# Encoder.net
KiCad netlist of a schematic drawn in EAGLE
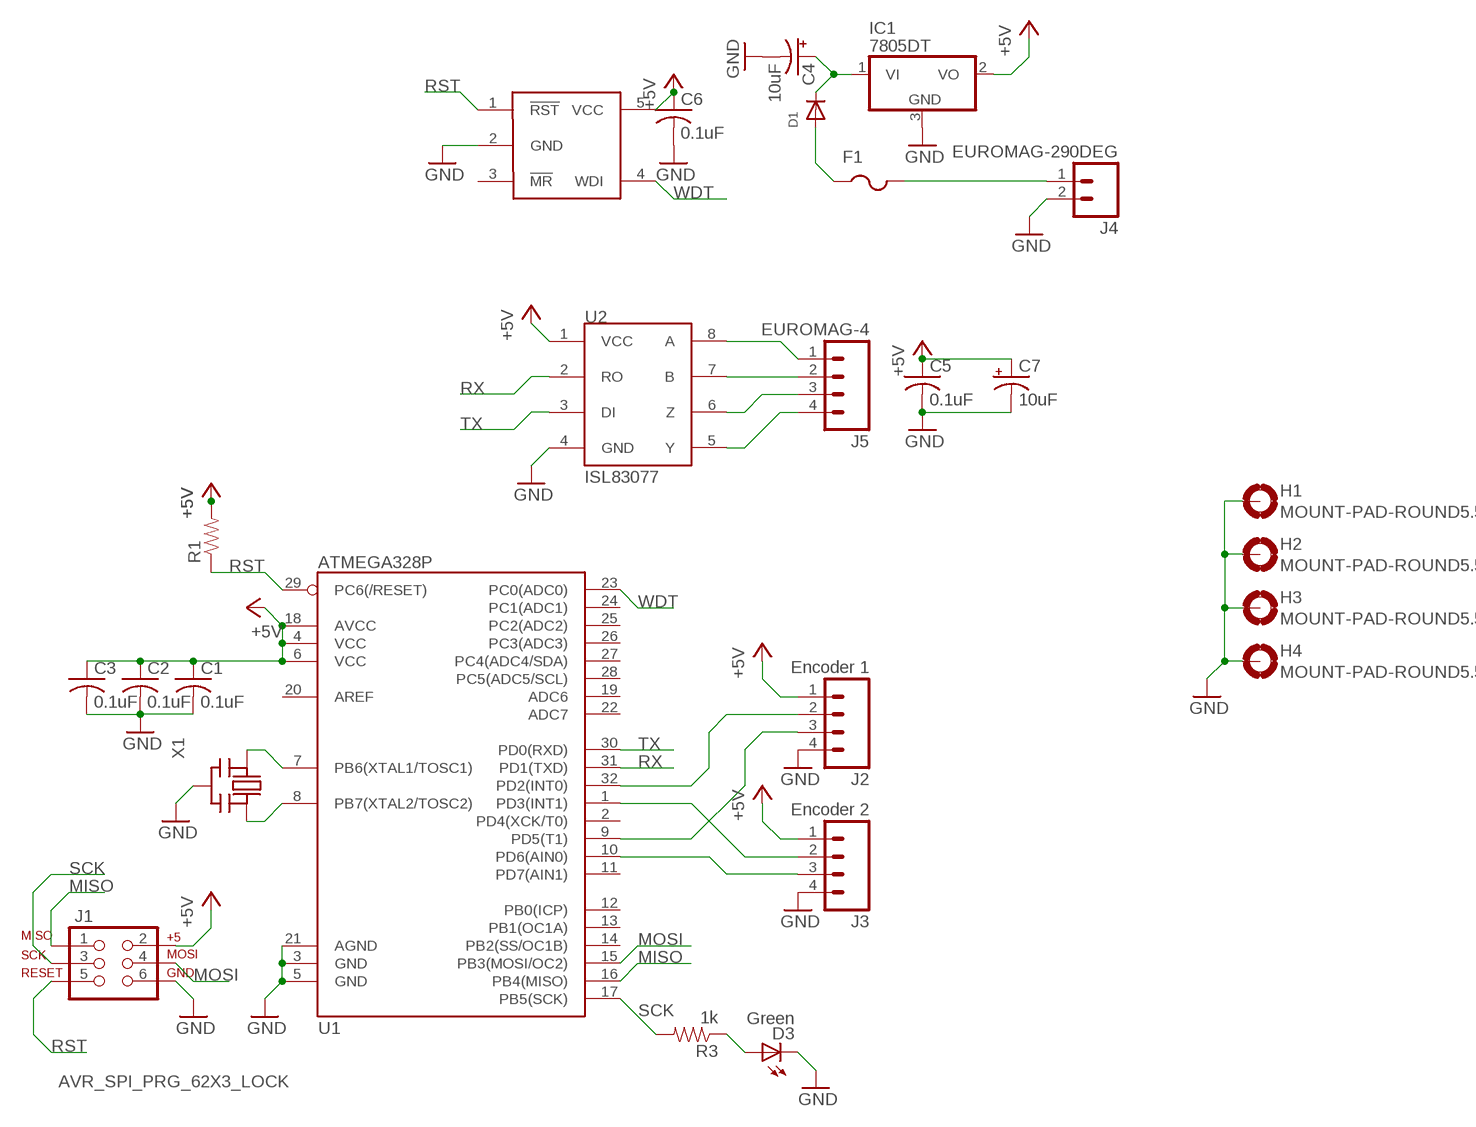
[diagram p0: schematic, sheet 1]

(export (version "E")
  (design (tool "Eeschema 10.0.6"))
  (components
    (comp (ref "C1")
      (value "0.1uF")
      (footprint "eagle-import:C0805")
      (libsource (lib "eagle-import") (part "C-USC0805"))
    )
    (comp (ref "C2")
      (value "0.1uF")
      (footprint "eagle-import:C0805")
      (libsource (lib "eagle-import") (part "C-USC0805"))
    )
    (comp (ref "C3")
      (value "0.1uF")
      (footprint "eagle-import:C0805")
      (libsource (lib "eagle-import") (part "C-USC0805"))
    )
    (comp (ref "C4")
      (value "10uF")
      (footprint "eagle-import:CT6032")
      (libsource (lib "eagle-import") (part "CPOL-USCT6032"))
    )
    (comp (ref "C5")
      (value "0.1uF")
      (footprint "eagle-import:C0805")
      (libsource (lib "eagle-import") (part "C-USC0805"))
    )
    (comp (ref "C6")
      (value "0.1uF")
      (footprint "eagle-import:C0805")
      (libsource (lib "eagle-import") (part "C-USC0805"))
    )
    (comp (ref "C7")
      (value "10uF")
      (footprint "eagle-import:CT6032")
      (libsource (lib "eagle-import") (part "CPOL-USCT6032"))
    )
    (comp (ref "D1")
      (value "DIODESMA")
      (footprint "eagle-import:SMADIODE")
      (libsource (lib "eagle-import") (part "DIODESMA"))
    )
    (comp (ref "D3")
      (value "Green")
      (footprint "eagle-import:LED-0603")
      (libsource (lib "eagle-import") (part "LED0603"))
    )
    (comp (ref "F1")
      (value "PTCFUSE-1206")
      (footprint "eagle-import:R1206")
      (libsource (lib "eagle-import") (part "PTCFUSE-1206"))
    )
    (comp (ref "H1")
      (value "MOUNT-PAD-ROUND5.5")
      (footprint "eagle-import:5,5-PAD")
      (libsource (lib "eagle-import") (part "MOUNT-PAD-ROUND5.5"))
    )
    (comp (ref "H2")
      (value "MOUNT-PAD-ROUND5.5")
      (footprint "eagle-import:5,5-PAD")
      (libsource (lib "eagle-import") (part "MOUNT-PAD-ROUND5.5"))
    )
    (comp (ref "H3")
      (value "MOUNT-PAD-ROUND5.5")
      (footprint "eagle-import:5,5-PAD")
      (libsource (lib "eagle-import") (part "MOUNT-PAD-ROUND5.5"))
    )
    (comp (ref "H4")
      (value "MOUNT-PAD-ROUND5.5")
      (footprint "eagle-import:5,5-PAD")
      (libsource (lib "eagle-import") (part "MOUNT-PAD-ROUND5.5"))
    )
    (comp (ref "IC1")
      (value "7805DT")
      (footprint "eagle-import:TO252")
      (libsource (lib "eagle-import") (part "78DT05"))
    )
    (comp (ref "J1")
      (value "AVR_SPI_PRG_62X3_LOCK")
      (footprint "eagle-import:2X3_LOCK")
      (libsource (lib "eagle-import") (part "AVR_SPI_PRG_62X3_LOCK"))
    )
    (comp (ref "J2")
      (value "Encoder 1")
      (footprint "eagle-import:M4")
      (libsource (lib "eagle-import") (part "EUROMAG-4"))
    )
    (comp (ref "J3")
      (value "Encoder 2")
      (footprint "eagle-import:M4")
      (libsource (lib "eagle-import") (part "EUROMAG-4"))
    )
    (comp (ref "J4")
      (value "EUROMAG-290DEG")
      (footprint "eagle-import:M2")
      (libsource (lib "eagle-import") (part "EUROMAG-290DEG"))
    )
    (comp (ref "J5")
      (value "EUROMAG-4")
      (footprint "eagle-import:M4")
      (libsource (lib "eagle-import") (part "EUROMAG-4"))
    )
    (comp (ref "R1")
      (value "RESISTOR0805-RES")
      (footprint "eagle-import:0805")
      (libsource (lib "eagle-import") (part "RESISTOR0805-RES"))
    )
    (comp (ref "R3")
      (value "1k")
      (footprint "eagle-import:0805")
      (libsource (lib "eagle-import") (part "RESISTOR0805-RES"))
    )
    (comp (ref "U$18")
      (value "MAX823")
      (footprint "eagle-import:SOT23-5L")
      (libsource (lib "eagle-import") (part "MAX823"))
    )
    (comp (ref "U1")
      (value "ATMEGA328P")
      (footprint "eagle-import:TQFP32-08")
      (libsource (lib "eagle-import") (part "ATMEGA328_SMT"))
    )
    (comp (ref "U2")
      (value "ISL83077")
      (footprint "eagle-import:SO08")
      (libsource (lib "eagle-import") (part "ISL83077"))
    )
    (comp (ref "X1")
      (value "CERMOSCILL-AWCSR")
      (footprint "eagle-import:AWCSR")
      (libsource (lib "eagle-import") (part "CERMOSCILL-AWCSR"))
    )
  )
  (nets
    (net (code "1") (name "+5V") (class "Default")
      (node (ref "C1") (pin "1") (pinfunction "1_1") (pintype "passive"))
      (node (ref "C2") (pin "1") (pinfunction "1_1") (pintype "passive"))
      (node (ref "C3") (pin "1") (pinfunction "1_1") (pintype "passive"))
      (node (ref "C5") (pin "1") (pinfunction "1_1") (pintype "passive"))
      (node (ref "C6") (pin "1") (pinfunction "1_1") (pintype "passive"))
      (node (ref "C7") (pin "+") (pinfunction "+_+") (pintype "passive"))
      (node (ref "IC1") (pin "2") (pinfunction "VO_2") (pintype "passive"))
      (node (ref "J1") (pin "2") (pinfunction "2_2") (pintype "passive"))
      (node (ref "J2") (pin "1") (pinfunction "1_1") (pintype "passive"))
      (node (ref "J3") (pin "1") (pinfunction "1_1") (pintype "passive"))
      (node (ref "R1") (pin "2") (pinfunction "2_2") (pintype "passive"))
      (node (ref "U$18") (pin "5") (pinfunction "VCC_5") (pintype "bidirectional"))
      (node (ref "U1") (pin "18") (pinfunction "AVCC_18") (pintype "bidirectional"))
      (node (ref "U1") (pin "4") (pinfunction "VCC_4") (pintype "bidirectional"))
      (node (ref "U1") (pin "6") (pinfunction "VCC_6") (pintype "bidirectional"))
      (node (ref "U2") (pin "1") (pinfunction "VCC_1") (pintype "bidirectional"))
    )
    (net (code "2") (name "/MISO") (class "Default")
      (node (ref "J1") (pin "1") (pinfunction "1_1") (pintype "passive"))
      (node (ref "U1") (pin "16") (pinfunction "PB4(MISO)_16") (pintype "bidirectional"))
    )
    (net (code "3") (name "/MOSI") (class "Default")
      (node (ref "J1") (pin "4") (pinfunction "4_4") (pintype "passive"))
      (node (ref "U1") (pin "15") (pinfunction "PB3(MOSI/OC2)_15") (pintype "bidirectional"))
    )
    (net (code "4") (name "/RST") (class "Default")
      (node (ref "J1") (pin "5") (pinfunction "5_5") (pintype "passive"))
      (node (ref "R1") (pin "1") (pinfunction "1_1") (pintype "passive"))
      (node (ref "U$18") (pin "1") (pinfunction "~{RST}_1") (pintype "bidirectional"))
      (node (ref "U1") (pin "29") (pinfunction "PC6(/RESET)_29") (pintype "bidirectional"))
    )
    (net (code "5") (name "/RX") (class "Default")
      (node (ref "U1") (pin "31") (pinfunction "PD1(TXD)_31") (pintype "bidirectional"))
      (node (ref "U2") (pin "2") (pinfunction "RO_2") (pintype "bidirectional"))
    )
    (net (code "6") (name "/SCK") (class "Default")
      (node (ref "J1") (pin "3") (pinfunction "3_3") (pintype "passive"))
      (node (ref "R3") (pin "2") (pinfunction "2_2") (pintype "passive"))
      (node (ref "U1") (pin "17") (pinfunction "PB5(SCK)_17") (pintype "bidirectional"))
    )
    (net (code "7") (name "/TX") (class "Default")
      (node (ref "U1") (pin "30") (pinfunction "PD0(RXD)_30") (pintype "bidirectional"))
      (node (ref "U2") (pin "3") (pinfunction "DI_3") (pintype "bidirectional"))
    )
    (net (code "8") (name "/WDT") (class "Default")
      (node (ref "U$18") (pin "4") (pinfunction "WDI_4") (pintype "bidirectional"))
      (node (ref "U1") (pin "23") (pinfunction "PC0(ADC0)_23") (pintype "bidirectional"))
    )
    (net (code "9") (name "GND") (class "Default")
      (node (ref "C1") (pin "2") (pinfunction "2_2") (pintype "passive"))
      (node (ref "C2") (pin "2") (pinfunction "2_2") (pintype "passive"))
      (node (ref "C3") (pin "2") (pinfunction "2_2") (pintype "passive"))
      (node (ref "C4") (pin "-") (pinfunction "-_-") (pintype "passive"))
      (node (ref "C5") (pin "2") (pinfunction "2_2") (pintype "passive"))
      (node (ref "C6") (pin "2") (pinfunction "2_2") (pintype "passive"))
      (node (ref "C7") (pin "-") (pinfunction "-_-") (pintype "passive"))
      (node (ref "D3") (pin "C") (pinfunction "C_C") (pintype "passive"))
      (node (ref "H1") (pin "B5,5") (pinfunction "MOUNT_B5,5") (pintype "passive"))
      (node (ref "H2") (pin "B5,5") (pinfunction "MOUNT_B5,5") (pintype "passive"))
      (node (ref "H3") (pin "B5,5") (pinfunction "MOUNT_B5,5") (pintype "passive"))
      (node (ref "H4") (pin "B5,5") (pinfunction "MOUNT_B5,5") (pintype "passive"))
      (node (ref "IC1") (pin "3") (pinfunction "GND_3") (pintype "passive"))
      (node (ref "J1") (pin "6") (pinfunction "6_6") (pintype "passive"))
      (node (ref "J2") (pin "4") (pinfunction "4_4") (pintype "passive"))
      (node (ref "J3") (pin "4") (pinfunction "4_4") (pintype "passive"))
      (node (ref "J4") (pin "2") (pinfunction "2_2") (pintype "passive"))
      (node (ref "U$18") (pin "2") (pinfunction "GND_2") (pintype "bidirectional"))
      (node (ref "U1") (pin "21") (pinfunction "AGND_21") (pintype "bidirectional"))
      (node (ref "U1") (pin "3") (pinfunction "GND_3") (pintype "bidirectional"))
      (node (ref "U1") (pin "5") (pinfunction "GND_5") (pintype "bidirectional"))
      (node (ref "U2") (pin "4") (pinfunction "GND_4") (pintype "bidirectional"))
      (node (ref "X1") (pin "2") (pinfunction "GND_2") (pintype "bidirectional"))
    )
    (net (code "10") (name "Net-(D1-PadA)") (class "Default")
      (node (ref "D1") (pin "A") (pinfunction "A_A") (pintype "passive"))
      (node (ref "F1") (pin "1") (pinfunction "1_1") (pintype "passive"))
    )
    (net (code "11") (name "Net-(D3-PadA)") (class "Default")
      (node (ref "D3") (pin "A") (pinfunction "A_A") (pintype "passive"))
      (node (ref "R3") (pin "1") (pinfunction "1_1") (pintype "passive"))
    )
    (net (code "12") (name "Net-(F1-Pad2)") (class "Default")
      (node (ref "F1") (pin "2") (pinfunction "2_2") (pintype "passive"))
      (node (ref "J4") (pin "1") (pinfunction "1_1") (pintype "passive"))
    )
    (net (code "13") (name "Net-(IC1-VI)") (class "Default")
      (node (ref "C4") (pin "+") (pinfunction "+_+") (pintype "passive"))
      (node (ref "D1") (pin "C") (pinfunction "C_C") (pintype "passive"))
      (node (ref "IC1") (pin "1") (pinfunction "VI_1") (pintype "input"))
    )
    (net (code "14") (name "Net-(U1-PB6(XTAL1{slash}TOSC1))") (class "Default")
      (node (ref "U1") (pin "7") (pinfunction "PB6(XTAL1/TOSC1)_7") (pintype "bidirectional"))
      (node (ref "X1") (pin "1") (pinfunction "IN_1") (pintype "bidirectional"))
    )
    (net (code "15") (name "Net-(U1-PB7(XTAL2{slash}TOSC2))") (class "Default")
      (node (ref "U1") (pin "8") (pinfunction "PB7(XTAL2/TOSC2)_8") (pintype "bidirectional"))
      (node (ref "X1") (pin "3") (pinfunction "OUT_3") (pintype "bidirectional"))
    )
    (net (code "16") (name "Net-(U1-PD2(INT0))") (class "Default")
      (node (ref "J2") (pin "2") (pinfunction "2_2") (pintype "passive"))
      (node (ref "U1") (pin "32") (pinfunction "PD2(INT0)_32") (pintype "bidirectional"))
    )
    (net (code "17") (name "Net-(U1-PD3(INT1))") (class "Default")
      (node (ref "J3") (pin "2") (pinfunction "2_2") (pintype "passive"))
      (node (ref "U1") (pin "1") (pinfunction "PD3(INT1)_1") (pintype "bidirectional"))
    )
    (net (code "18") (name "Net-(U1-PD5(T1))") (class "Default")
      (node (ref "J2") (pin "3") (pinfunction "3_3") (pintype "passive"))
      (node (ref "U1") (pin "9") (pinfunction "PD5(T1)_9") (pintype "bidirectional"))
    )
    (net (code "19") (name "Net-(U1-PD6(AIN0))") (class "Default")
      (node (ref "J3") (pin "3") (pinfunction "3_3") (pintype "passive"))
      (node (ref "U1") (pin "10") (pinfunction "PD6(AIN0)_10") (pintype "bidirectional"))
    )
    (net (code "20") (name "Net-(U2-A)") (class "Default")
      (node (ref "J5") (pin "1") (pinfunction "1_1") (pintype "passive"))
      (node (ref "U2") (pin "8") (pinfunction "A_8") (pintype "bidirectional"))
    )
    (net (code "21") (name "Net-(U2-B)") (class "Default")
      (node (ref "J5") (pin "2") (pinfunction "2_2") (pintype "passive"))
      (node (ref "U2") (pin "7") (pinfunction "B_7") (pintype "bidirectional"))
    )
    (net (code "22") (name "Net-(U2-Y)") (class "Default")
      (node (ref "J5") (pin "4") (pinfunction "4_4") (pintype "passive"))
      (node (ref "U2") (pin "5") (pinfunction "Y_5") (pintype "bidirectional"))
    )
    (net (code "23") (name "Net-(U2-Z)") (class "Default")
      (node (ref "J5") (pin "3") (pinfunction "3_3") (pintype "passive"))
      (node (ref "U2") (pin "6") (pinfunction "Z_6") (pintype "bidirectional"))
    )
    (net (code "24") (name "unconnected-(U$18-~{MR}-Pad3)") (class "Default")
      (node (ref "U$18") (pin "3") (pinfunction "~{MR}_3") (pintype "bidirectional"))
    )
    (net (code "25") (name "unconnected-(U1-ADC6-Pad19)") (class "Default")
      (node (ref "U1") (pin "19") (pinfunction "ADC6_19") (pintype "bidirectional"))
    )
    (net (code "26") (name "unconnected-(U1-ADC7-Pad22)") (class "Default")
      (node (ref "U1") (pin "22") (pinfunction "ADC7_22") (pintype "bidirectional"))
    )
    (net (code "27") (name "unconnected-(U1-AREF-Pad20)") (class "Default")
      (node (ref "U1") (pin "20") (pinfunction "AREF_20") (pintype "bidirectional"))
    )
    (net (code "28") (name "unconnected-(U1-PB0(ICP)-Pad12)") (class "Default")
      (node (ref "U1") (pin "12") (pinfunction "PB0(ICP)_12") (pintype "bidirectional"))
    )
    (net (code "29") (name "unconnected-(U1-PB1(OC1A)-Pad13)") (class "Default")
      (node (ref "U1") (pin "13") (pinfunction "PB1(OC1A)_13") (pintype "bidirectional"))
    )
    (net (code "30") (name "unconnected-(U1-PB2(SS{slash}OC1B)-Pad14)") (class "Default")
      (node (ref "U1") (pin "14") (pinfunction "PB2(SS/OC1B)_14") (pintype "bidirectional"))
    )
    (net (code "31") (name "unconnected-(U1-PC1(ADC1)-Pad24)") (class "Default")
      (node (ref "U1") (pin "24") (pinfunction "PC1(ADC1)_24") (pintype "bidirectional"))
    )
    (net (code "32") (name "unconnected-(U1-PC2(ADC2)-Pad25)") (class "Default")
      (node (ref "U1") (pin "25") (pinfunction "PC2(ADC2)_25") (pintype "bidirectional"))
    )
    (net (code "33") (name "unconnected-(U1-PC3(ADC3)-Pad26)") (class "Default")
      (node (ref "U1") (pin "26") (pinfunction "PC3(ADC3)_26") (pintype "bidirectional"))
    )
    (net (code "34") (name "unconnected-(U1-PC4(ADC4{slash}SDA)-Pad27)") (class "Default")
      (node (ref "U1") (pin "27") (pinfunction "PC4(ADC4/SDA)_27") (pintype "bidirectional"))
    )
    (net (code "35") (name "unconnected-(U1-PC5(ADC5{slash}SCL)-Pad28)") (class "Default")
      (node (ref "U1") (pin "28") (pinfunction "PC5(ADC5/SCL)_28") (pintype "bidirectional"))
    )
    (net (code "36") (name "unconnected-(U1-PD4(XCK{slash}T0)-Pad2)") (class "Default")
      (node (ref "U1") (pin "2") (pinfunction "PD4(XCK/T0)_2") (pintype "bidirectional"))
    )
    (net (code "37") (name "unconnected-(U1-PD7(AIN1)-Pad11)") (class "Default")
      (node (ref "U1") (pin "11") (pinfunction "PD7(AIN1)_11") (pintype "bidirectional"))
    )
  )
)
